# MOTOR_DRIVE.net
KiCad netlist of a schematic drawn in Altium Designer
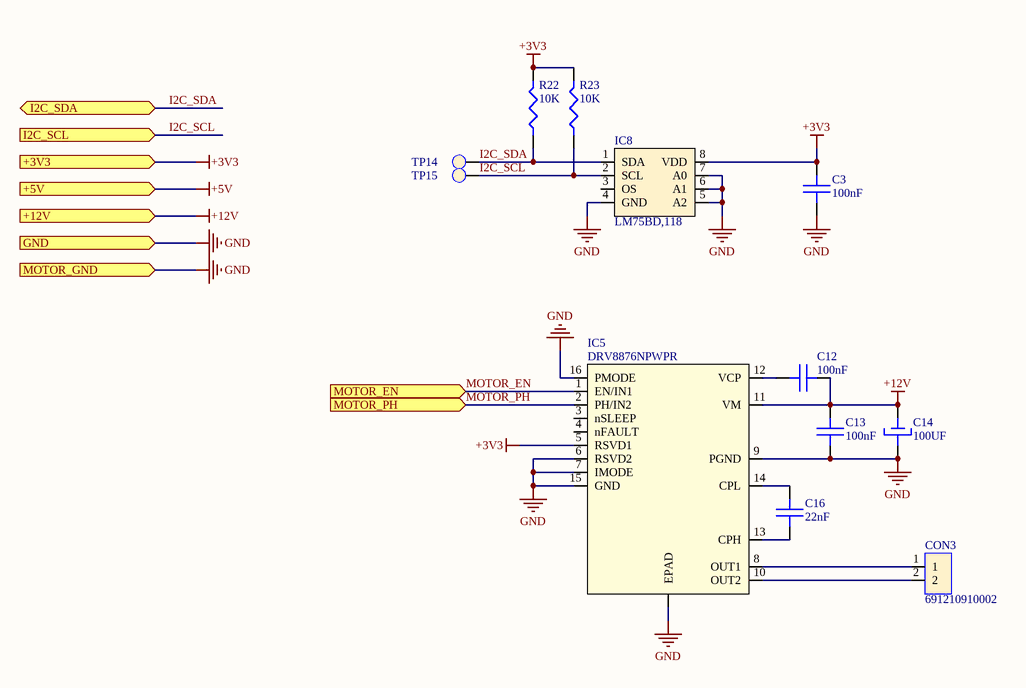
[diagram p0: MOTOR_DRIVE.SchDoc]

(export (version "E")
  (design (tool "Eeschema 10.0.6"))
  (components
    (comp (ref "C3")
      (value "100nF")
      (footprint "C0402")
      (description "100nF ,10V ,X7R ,0402")
      (fields
        (field (name "MANUFACTURER") "Yageo")
        (field (name "MANUFACTURER PART NUMBER") "CC0402KRX7R6BB104")
      )
      (libsource (lib "Capacitor") (part "CC0402KRX7R6BB104"))
    )
    (comp (ref "C12")
      (value "100nF")
      (footprint "C0603")
      (description "100nF, 25V, X7R, 0603")
      (fields
        (field (name "MANUFACTURER") "Yageo")
        (field (name "MANUFACTURER PART NUMBER") "CC0603KRX7R8BB104")
      )
      (libsource (lib "Capacitor") (part "CC0603KRX7R8BB104"))
    )
    (comp (ref "C13")
      (value "100nF")
      (footprint "C0603")
      (description "100nF, 25V, X7R, 0603")
      (fields
        (field (name "MANUFACTURER") "Yageo")
        (field (name "MANUFACTURER PART NUMBER") "CC0603KRX7R8BB104")
      )
      (libsource (lib "Capacitor") (part "CC0603KRX7R8BB104"))
    )
    (comp (ref "C14")
      (value "100UF")
      (footprint "6mm Aliminyum Smd")
      (description "100uF, 16V, ELC, 6.3mm SMD")
      (fields
        (field (name "MANUFACTURER") "Nichicon")
        (field (name "MANUFACTURER PART NUMBER") "UWX1C101MCL1GB")
      )
      (libsource (lib "Capacitor") (part "UWX1C101MCL1GB"))
    )
    (comp (ref "C16")
      (value "22nF")
      (footprint "C0805")
      (description "22nF, 50 V, X7R, 0805")
      (fields
        (field (name "MANUFACTURER") "Yageo")
        (field (name "MANUFACTURER PART NUMBER") "CC0805KRX7R9BB223")
      )
      (libsource (lib "Capacitor") (part "CC0805KRX7R9BB223"))
    )
    (comp (ref "CON3")
      (value "691210910002")
      (footprint "691210910002")
      (description "2.54 Mm Terminal Block, Horizont")
      (fields (field (name "MANUFACTURER") "Wurth Electronics"))
      (libsource (lib "Connectors") (part "691210910002"))
    )
    (comp (ref "IC5")
      (value "DRV8876NPWPR")
      (footprint "HTSSOP16_4P4X5_TEX-M")
      (description "37-V, 3.5-A brushed DC motor driver 16-HTSSOP -40 to 125")
      (fields (field (name "MANUFACTURER") "Texas Instruments"))
      (libsource (lib "IntegratedCircuit") (part "DRV8876NPWPR"))
    )
    (comp (ref "IC8")
      (value "LM75BD,118")
      (footprint "SO08")
      (description "LM75 Series 5.5 V I2C Digital Temperature Sensor and Thermal Watchdog - SOIC-8")
      (fields (field (name "MANUFACTURER") "NXP Semiconductors"))
      (libsource (lib "Sensor") (part "LM75BD,118"))
    )
    (comp (ref "R22")
      (value "10K")
      (footprint "R0402")
      (description "10K, %1, 1/16W, 0402")
      (fields
        (field (name "MANUFACTURER") "YAGEO")
        (field (name "MANUFACTURER PART NUMBER") "RC0402FR-0710KL")
      )
      (libsource (lib "Resistor") (part "RC0402FR-0710KL"))
    )
    (comp (ref "R23")
      (value "10K")
      (footprint "R0402")
      (description "10K, %1, 1/16W, 0402")
      (fields
        (field (name "MANUFACTURER") "YAGEO")
        (field (name "MANUFACTURER PART NUMBER") "RC0402FR-0710KL")
      )
      (libsource (lib "Resistor") (part "RC0402FR-0710KL"))
    )
    (comp (ref "TP14")
      (value "TestPoint1")
      (footprint "SMD_1mmPoint")
      (description "test ölçüm noktası")
      (fields (field (name "MANUFACTURER") "NO BOM DEVICE"))
      (libsource (lib "Connectors") (part "TestPoint1"))
    )
    (comp (ref "TP15")
      (value "TestPoint1")
      (footprint "SMD_1mmPoint")
      (description "test ölçüm noktası")
      (fields (field (name "MANUFACTURER") "NO BOM DEVICE"))
      (libsource (lib "Connectors") (part "TestPoint1"))
    )
  )
  (nets
    (net (code "1") (name "+3V3") (class "Default")
      (node (ref "C3") (pin "2") (pintype "passive"))
      (node (ref "IC5") (pin "5") (pinfunction "RSVD1_5") (pintype "passive"))
      (node (ref "IC8") (pin "8") (pinfunction "VDD_8") (pintype "passive"))
      (node (ref "R22") (pin "2") (pinfunction "2_2") (pintype "passive"))
      (node (ref "R23") (pin "2") (pinfunction "2_2") (pintype "passive"))
    )
    (net (code "3") (name "+12V") (class "Default")
      (node (ref "C12") (pin "2") (pintype "passive"))
      (node (ref "C13") (pin "2") (pintype "passive"))
      (node (ref "C14") (pin "1") (pintype "passive"))
      (node (ref "IC5") (pin "11") (pinfunction "VM_11") (pintype "passive"))
    )
    (net (code "4") (name "/I2C_SCL") (class "Default")
      (node (ref "IC8") (pin "2") (pinfunction "SCL_2") (pintype "passive"))
      (node (ref "R23") (pin "1") (pinfunction "1_1") (pintype "passive"))
      (node (ref "TP15") (pin "1") (pinfunction "1_1") (pintype "passive"))
    )
    (net (code "5") (name "/I2C_SDA") (class "Default")
      (node (ref "IC8") (pin "1") (pinfunction "SDA_1") (pintype "passive"))
      (node (ref "R22") (pin "1") (pinfunction "1_1") (pintype "passive"))
      (node (ref "TP14") (pin "1") (pinfunction "1_1") (pintype "passive"))
    )
    (net (code "6") (name "/MOTOR_EN") (class "Default")
      (node (ref "IC5") (pin "1") (pinfunction "EN/IN1_1") (pintype "passive"))
    )
    (net (code "7") (name "/MOTOR_PH") (class "Default")
      (node (ref "IC5") (pin "2") (pinfunction "PH/IN2_2") (pintype "passive"))
    )
    (net (code "8") (name "GND") (class "Default")
      (node (ref "C13") (pin "1") (pintype "passive"))
      (node (ref "C14") (pin "2") (pintype "passive"))
      (node (ref "C3") (pin "1") (pintype "passive"))
      (node (ref "IC5") (pin "15") (pinfunction "GND_15") (pintype "passive"))
      (node (ref "IC5") (pin "16") (pinfunction "PMODE_16") (pintype "passive"))
      (node (ref "IC5") (pin "6") (pinfunction "RSVD2_6") (pintype "passive"))
      (node (ref "IC5") (pin "7") (pinfunction "IMODE_7") (pintype "passive"))
      (node (ref "IC5") (pin "9") (pinfunction "PGND_9") (pintype "passive"))
      (node (ref "IC5") (pin "EPAD") (pinfunction "EPAD_EPAD") (pintype "passive"))
      (node (ref "IC8") (pin "4") (pinfunction "GND_4") (pintype "passive"))
      (node (ref "IC8") (pin "5") (pinfunction "A2_5") (pintype "passive"))
      (node (ref "IC8") (pin "6") (pinfunction "A1_6") (pintype "passive"))
      (node (ref "IC8") (pin "7") (pinfunction "A0_7") (pintype "passive"))
    )
    (net (code "9") (name "Net-(IC5-CPH)") (class "Default")
      (node (ref "C16") (pin "1") (pintype "passive"))
      (node (ref "IC5") (pin "13") (pinfunction "CPH_13") (pintype "passive"))
    )
    (net (code "10") (name "Net-(IC5-CPL)") (class "Default")
      (node (ref "C16") (pin "2") (pintype "passive"))
      (node (ref "IC5") (pin "14") (pinfunction "CPL_14") (pintype "passive"))
    )
    (net (code "11") (name "Net-(IC5-OUT1)") (class "Default")
      (node (ref "CON3") (pin "1") (pinfunction "1_1") (pintype "passive"))
      (node (ref "IC5") (pin "8") (pinfunction "OUT1_8") (pintype "passive"))
    )
    (net (code "12") (name "Net-(IC5-OUT2)") (class "Default")
      (node (ref "CON3") (pin "2") (pinfunction "2_2") (pintype "passive"))
      (node (ref "IC5") (pin "10") (pinfunction "OUT2_10") (pintype "passive"))
    )
    (net (code "13") (name "Net-(IC5-VCP)") (class "Default")
      (node (ref "C12") (pin "1") (pintype "passive"))
      (node (ref "IC5") (pin "12") (pinfunction "VCP_12") (pintype "passive"))
    )
    (net (code "14") (name "unconnected-(IC5-nFAULT-Pad4)") (class "Default")
      (node (ref "IC5") (pin "4") (pinfunction "nFAULT_4") (pintype "passive"))
    )
    (net (code "15") (name "unconnected-(IC5-nSLEEP-Pad3)") (class "Default")
      (node (ref "IC5") (pin "3") (pinfunction "nSLEEP_3") (pintype "passive"))
    )
    (net (code "16") (name "unconnected-(IC8-OS-Pad3)") (class "Default")
      (node (ref "IC8") (pin "3") (pinfunction "OS_3") (pintype "passive"))
    )
  )
)
